# DB10005_USBSerial.net
KiCad netlist of a schematic drawn in Altium Designer
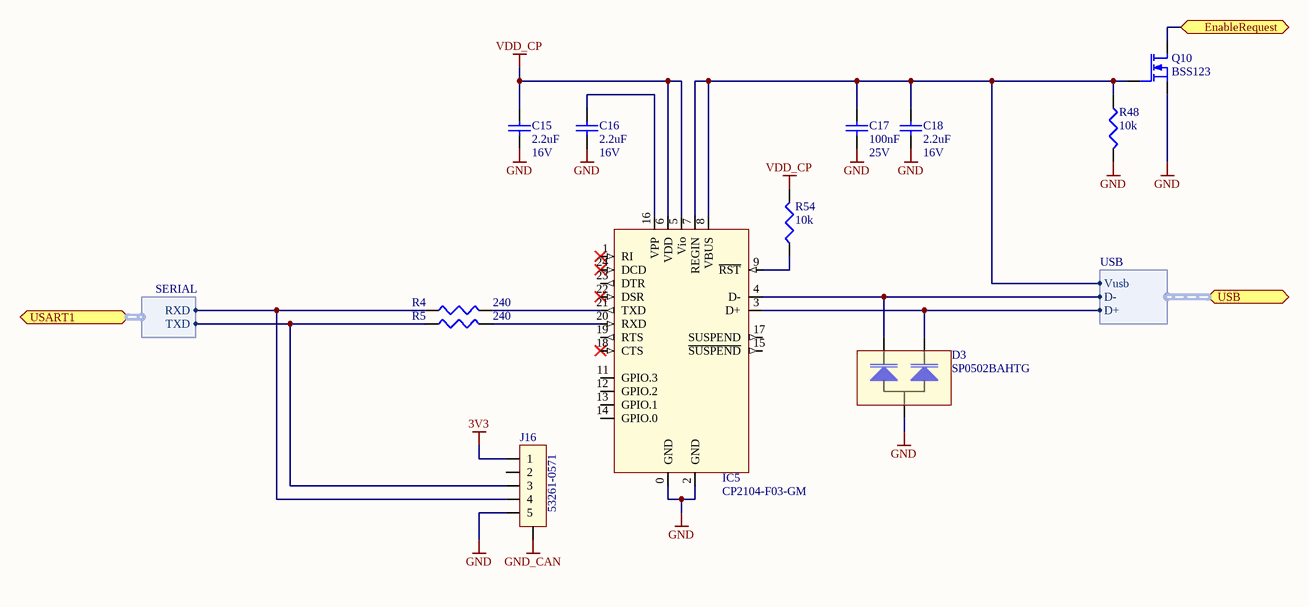
[diagram p0: DB10005_USBSerial.SchDoc]

(export (version "E")
  (design (tool "Eeschema 10.0.6"))
  (components
    (comp (ref "C15")
      (value "2.2uF")
      (footprint "C0603")
      (description "Capacitor, 2.2uF, 16V, X5R")
      (fields (field (name "VOLTAGE RATING") "16V"))
      (libsource (lib "AR_Capacitors_Ceramic") (part "2.2uF/0603/CER/16V"))
    )
    (comp (ref "C16")
      (value "2.2uF")
      (footprint "C0603")
      (description "Capacitor, 2.2uF, 16V, X5R")
      (fields (field (name "VOLTAGE RATING") "16V"))
      (libsource (lib "AR_Capacitors_Ceramic") (part "2.2uF/0603/CER/16V"))
    )
    (comp (ref "C17")
      (value "100nF")
      (footprint "C0402")
      (description "Capacitor, 100nF, 25V, X7R")
      (fields (field (name "VOLTAGE RATING") "25V"))
      (libsource (lib "AR_Capacitors_Ceramic") (part "100nF/0402/CER/25V"))
    )
    (comp (ref "C18")
      (value "2.2uF")
      (footprint "C0603")
      (description "Capacitor, 2.2uF, 16V, X5R")
      (fields (field (name "VOLTAGE RATING") "16V"))
      (libsource (lib "AR_Capacitors_Ceramic") (part "2.2uF/0603/CER/16V"))
    )
    (comp (ref "D3")
      (value "SP0502BAHTG")
      (footprint "SOT23")
      (description "Diode TVS Dual, Vrwm: 5.5V Vc: 8V")
      (libsource (lib "AR_Diodes") (part "SP0502BAHTG"))
    )
    (comp (ref "IC5")
      (value "CP2104-F03-GM")
      (footprint "QFN24")
      (description "USB to UART converter")
      (libsource (lib "AR_ICs") (part "CP2104-F03-GM"))
    )
    (comp (ref "J16")
      (value "53261-0571")
      (footprint "53261-0571")
      (description "PicoBlade 53261 Series, 5Pin, Right Angle")
      (libsource (lib "AR_Connectors") (part "53261-0571"))
    )
    (comp (ref "Q10")
      (value "BSS123")
      (footprint "SOT-23")
      (description "Mosfet, N-channel, Vds:100V, Id:0.15A, Vgs-th:2.8V, Rds-on:3.5ohm")
      (libsource (lib "AR_Mosfets") (part "BSS123"))
    )
    (comp (ref "R4")
      (value "240")
      (footprint "0402")
      (description "Resistor, 240, 0.1%, 0.0625W, 50V, 100PPM, 0402")
      (libsource (lib "AR_Resistors_SMD") (part "240/0402/0063W/50V"))
    )
    (comp (ref "R5")
      (value "240")
      (footprint "0402")
      (description "Resistor, 240, 0.1%, 0.0625W, 50V, 100PPM, 0402")
      (libsource (lib "AR_Resistors_SMD") (part "240/0402/0063W/50V"))
    )
    (comp (ref "R48")
      (value "10k")
      (footprint "0402")
      (description "Resistor, 10k, 0.1%, 0.0625W, 50V, 100PPM, 0402")
      (libsource (lib "AR_Resistors_SMD") (part "10k/0402/0063W/50V"))
    )
    (comp (ref "R54")
      (value "10k")
      (footprint "0402")
      (description "Resistor, 10k, 0.1%, 0.0625W, 50V, 100PPM, 0402")
      (libsource (lib "AR_Resistors_SMD") (part "10k/0402/0063W/50V"))
    )
  )
  (nets
    (net (code "3") (name "/EnableRequest") (class "Default")
      (node (ref "Q10") (pin "D") (pinfunction "D_D") (pintype "passive"))
    )
    (net (code "6") (name "3V3") (class "Default")
      (node (ref "J16") (pin "1") (pinfunction "1_1") (pintype "passive"))
    )
    (net (code "7") (name "GND") (class "Default")
      (node (ref "C15") (pin "1") (pinfunction "1_1") (pintype "passive"))
      (node (ref "C16") (pin "1") (pinfunction "1_1") (pintype "passive"))
      (node (ref "C17") (pin "1") (pinfunction "1_1") (pintype "passive"))
      (node (ref "C18") (pin "1") (pinfunction "1_1") (pintype "passive"))
      (node (ref "D3") (pin "A") (pinfunction "A_A") (pintype "passive"))
      (node (ref "IC5") (pin "0") (pinfunction "GND_0") (pintype "power_in"))
      (node (ref "IC5") (pin "2") (pinfunction "GND_2") (pintype "power_in"))
      (node (ref "J16") (pin "5") (pinfunction "5_5") (pintype "passive"))
      (node (ref "Q10") (pin "S") (pinfunction "S_S") (pintype "passive"))
      (node (ref "R48") (pin "1") (pinfunction "1_1") (pintype "passive"))
    )
    (net (code "8") (name "GND_CAN") (class "Default")
      (node (ref "J16") (pin "0") (pinfunction "SHLD_0") (pintype "passive"))
    )
    (net (code "9") (name "Net-(IC5-D+)") (class "Default")
      (node (ref "D3") (pin "K2") (pinfunction "K2_K2") (pintype "passive"))
      (node (ref "IC5") (pin "3") (pinfunction "D+_3") (pintype "bidirectional"))
    )
    (net (code "10") (name "Net-(IC5-D-)") (class "Default")
      (node (ref "D3") (pin "K1") (pinfunction "K1_K1") (pintype "passive"))
      (node (ref "IC5") (pin "4") (pinfunction "D-_4") (pintype "bidirectional"))
    )
    (net (code "11") (name "Net-(IC5-REGIN)") (class "Default")
      (node (ref "C17") (pin "2") (pinfunction "2_2") (pintype "passive"))
      (node (ref "C18") (pin "2") (pinfunction "2_2") (pintype "passive"))
      (node (ref "IC5") (pin "7") (pinfunction "REGIN_7") (pintype "power_in"))
      (node (ref "IC5") (pin "8") (pinfunction "VBUS_8") (pintype "power_in"))
      (node (ref "Q10") (pin "G") (pinfunction "G_G") (pintype "passive"))
      (node (ref "R48") (pin "2") (pinfunction "2_2") (pintype "passive"))
    )
    (net (code "12") (name "Net-(IC5-RXD)") (class "Default")
      (node (ref "IC5") (pin "20") (pinfunction "RXD_20") (pintype "input"))
      (node (ref "R5") (pin "2") (pinfunction "2_2") (pintype "passive"))
    )
    (net (code "13") (name "Net-(IC5-TXD)") (class "Default")
      (node (ref "IC5") (pin "21") (pinfunction "TXD_21") (pintype "output"))
      (node (ref "R4") (pin "2") (pinfunction "2_2") (pintype "passive"))
    )
    (net (code "14") (name "Net-(IC5-VPP)") (class "Default")
      (node (ref "C16") (pin "2") (pinfunction "2_2") (pintype "passive"))
      (node (ref "IC5") (pin "16") (pinfunction "VPP_16") (pintype "power_in"))
    )
    (net (code "15") (name "Net-(IC5-~{RST})") (class "Default")
      (node (ref "IC5") (pin "9") (pinfunction "~{RST}_9") (pintype "input"))
      (node (ref "R54") (pin "1") (pinfunction "1_1") (pintype "passive"))
    )
    (net (code "16") (name "Net-(J16-Pad3)") (class "Default")
      (node (ref "J16") (pin "3") (pinfunction "3_3") (pintype "passive"))
      (node (ref "R5") (pin "1") (pinfunction "1_1") (pintype "passive"))
    )
    (net (code "17") (name "Net-(J16-Pad4)") (class "Default")
      (node (ref "J16") (pin "4") (pinfunction "4_4") (pintype "passive"))
      (node (ref "R4") (pin "1") (pinfunction "1_1") (pintype "passive"))
    )
    (net (code "18") (name "VDD_CP") (class "Default")
      (node (ref "C15") (pin "2") (pinfunction "2_2") (pintype "passive"))
      (node (ref "IC5") (pin "5") (pinfunction "Vio_5") (pintype "passive"))
      (node (ref "IC5") (pin "6") (pinfunction "VDD_6") (pintype "power_in"))
      (node (ref "R54") (pin "2") (pinfunction "2_2") (pintype "passive"))
    )
    (net (code "19") (name "unconnected-(IC5-CTS-Pad18)") (class "Default")
      (node (ref "IC5") (pin "18") (pinfunction "CTS_18") (pintype "input+no_connect"))
    )
    (net (code "20") (name "unconnected-(IC5-DCD-Pad24)") (class "Default")
      (node (ref "IC5") (pin "24") (pinfunction "DCD_24") (pintype "input+no_connect"))
    )
    (net (code "21") (name "unconnected-(IC5-DSR-Pad22)") (class "Default")
      (node (ref "IC5") (pin "22") (pinfunction "DSR_22") (pintype "input+no_connect"))
    )
    (net (code "22") (name "unconnected-(IC5-DTR-Pad23)") (class "Default")
      (node (ref "IC5") (pin "23") (pinfunction "DTR_23") (pintype "output"))
    )
    (net (code "23") (name "unconnected-(IC5-GPIO.0-Pad14)") (class "Default")
      (node (ref "IC5") (pin "14") (pinfunction "GPIO.0_14") (pintype "passive"))
    )
    (net (code "24") (name "unconnected-(IC5-GPIO.1-Pad13)") (class "Default")
      (node (ref "IC5") (pin "13") (pinfunction "GPIO.1_13") (pintype "passive"))
    )
    (net (code "25") (name "unconnected-(IC5-GPIO.2-Pad12)") (class "Default")
      (node (ref "IC5") (pin "12") (pinfunction "GPIO.2_12") (pintype "passive"))
    )
    (net (code "26") (name "unconnected-(IC5-GPIO.3-Pad11)") (class "Default")
      (node (ref "IC5") (pin "11") (pinfunction "GPIO.3_11") (pintype "passive"))
    )
    (net (code "27") (name "unconnected-(IC5-RI-Pad1)") (class "Default")
      (node (ref "IC5") (pin "1") (pinfunction "RI_1") (pintype "input+no_connect"))
    )
    (net (code "28") (name "unconnected-(IC5-RTS-Pad19)") (class "Default")
      (node (ref "IC5") (pin "19") (pinfunction "RTS_19") (pintype "output"))
    )
    (net (code "29") (name "unconnected-(IC5-SUSPEND-Pad17)") (class "Default")
      (node (ref "IC5") (pin "17") (pinfunction "SUSPEND_17") (pintype "output"))
    )
    (net (code "30") (name "unconnected-(IC5-~{SUSPEND}-Pad15)") (class "Default")
      (node (ref "IC5") (pin "15") (pinfunction "~{SUSPEND}_15") (pintype "output"))
    )
    (net (code "31") (name "unconnected-(J16-Pad2)") (class "Default")
      (node (ref "J16") (pin "2") (pinfunction "2_2") (pintype "passive"))
    )
  )
)
